# lighting.net
KiCad netlist of a schematic drawn in EAGLE
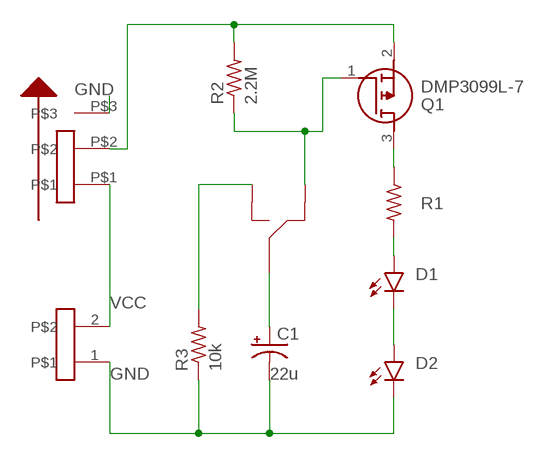
[diagram p0: schematic, sheet 1]

(export (version "E")
  (design (tool "Eeschema 10.0.6"))
  (components
    (comp (ref "C1")
      (value "WE-CAP")
      (footprint "eagle-import:WE-CAP")
      (fields (field (name "C") "22u"))
      (libsource (lib "eagle-import") (part "WE-CAP"))
    )
    (comp (ref "D1")
      (value "LUXEON2835C")
      (footprint "eagle-import:LUXEON2835C")
      (libsource (lib "eagle-import") (part "LUXEON2835C"))
    )
    (comp (ref "D2")
      (value "LUXEON2835C")
      (footprint "eagle-import:LUXEON2835C")
      (libsource (lib "eagle-import") (part "LUXEON2835C"))
    )
    (comp (ref "J1")
      (value "22-05-3021")
      (footprint "eagle-import:7395-02")
      (libsource (lib "eagle-import") (part "22-05-3021"))
    )
    (comp (ref "Q1")
      (value "DMP3099L-7")
      (footprint "eagle-import:SOT96P240X120-3N")
      (fields (field (name "MOUSER_PART_NUMBER") "621-DMP3099L-7"))
      (libsource (lib "eagle-import") (part "DMP3099L-7"))
    )
    (comp (ref "R1")
      (value "R-US_R1210")
      (footprint "eagle-import:R1210")
      (libsource (lib "eagle-import") (part "R-US_R1210"))
    )
    (comp (ref "R2")
      (value "2.2M")
      (footprint "eagle-import:R1206")
      (libsource (lib "eagle-import") (part "R-US_R1206"))
    )
    (comp (ref "R3")
      (value "10k")
      (footprint "eagle-import:R1206")
      (libsource (lib "eagle-import") (part "R-US_R1206"))
    )
    (comp (ref "S2")
      (value "CL-SB-12B-01T")
      (footprint "eagle-import:CL-SB-12B-01T")
      (libsource (lib "eagle-import") (part "CL-SB-12B-01T"))
    )
    (comp (ref "U$1")
      (value "KSK-1C90U")
      (footprint "eagle-import:KSK-1C90U")
      (libsource (lib "eagle-import") (part "KSK-1C90U"))
    )
  )
  (nets
    (net (code "1") (name "/GND") (class "Default")
      (node (ref "C1") (pin "-") (pinfunction "-_-") (pintype "passive"))
      (node (ref "D2") (pin "-") (pinfunction "C_-") (pintype "passive"))
      (node (ref "J1") (pin "1") (pinfunction "P$1_1") (pintype "bidirectional"))
      (node (ref "R3") (pin "1") (pinfunction "1_1") (pintype "passive"))
      (node (ref "S2") (pin "P$3") (pinfunction "P$3_P$3") (pintype "bidirectional"))
    )
    (net (code "2") (name "/VCC") (class "Default")
      (node (ref "J1") (pin "2") (pinfunction "P$2_2") (pintype "bidirectional"))
      (node (ref "S2") (pin "P$1") (pinfunction "P$1_P$1") (pintype "bidirectional"))
    )
    (net (code "3") (name "Net-(C1-Pad+)") (class "Default")
      (node (ref "C1") (pin "+") (pinfunction "+_+") (pintype "passive"))
      (node (ref "U$1") (pin "COM") (pinfunction "COM_COM") (pintype "bidirectional"))
    )
    (net (code "4") (name "Net-(D1-A)") (class "Default")
      (node (ref "D1") (pin "+") (pinfunction "A_+") (pintype "passive"))
      (node (ref "R1") (pin "2") (pinfunction "2_2") (pintype "passive"))
    )
    (net (code "5") (name "Net-(D1-C)") (class "Default")
      (node (ref "D1") (pin "-") (pinfunction "C_-") (pintype "passive"))
      (node (ref "D2") (pin "+") (pinfunction "A_+") (pintype "passive"))
    )
    (net (code "6") (name "Net-(Q1-D)") (class "Default")
      (node (ref "Q1") (pin "3") (pinfunction "D_3") (pintype "bidirectional"))
      (node (ref "R1") (pin "1") (pinfunction "1_1") (pintype "passive"))
    )
    (net (code "7") (name "Net-(Q1-G)") (class "Default")
      (node (ref "Q1") (pin "1") (pinfunction "G_1") (pintype "bidirectional"))
      (node (ref "R2") (pin "1") (pinfunction "1_1") (pintype "passive"))
      (node (ref "U$1") (pin "NC") (pinfunction "NC_NC") (pintype "bidirectional"))
    )
    (net (code "8") (name "Net-(Q1-S)") (class "Default")
      (node (ref "Q1") (pin "2") (pinfunction "S_2") (pintype "bidirectional"))
      (node (ref "R2") (pin "2") (pinfunction "2_2") (pintype "passive"))
      (node (ref "S2") (pin "P$2") (pinfunction "P$2_P$2") (pintype "bidirectional"))
    )
    (net (code "9") (name "Net-(R3-Pad2)") (class "Default")
      (node (ref "R3") (pin "2") (pinfunction "2_2") (pintype "passive"))
      (node (ref "U$1") (pin "NO") (pinfunction "NO_NO") (pintype "bidirectional"))
    )
  )
)
